# TLC5947_Breakout.net
KiCad netlist of a schematic drawn in EAGLE
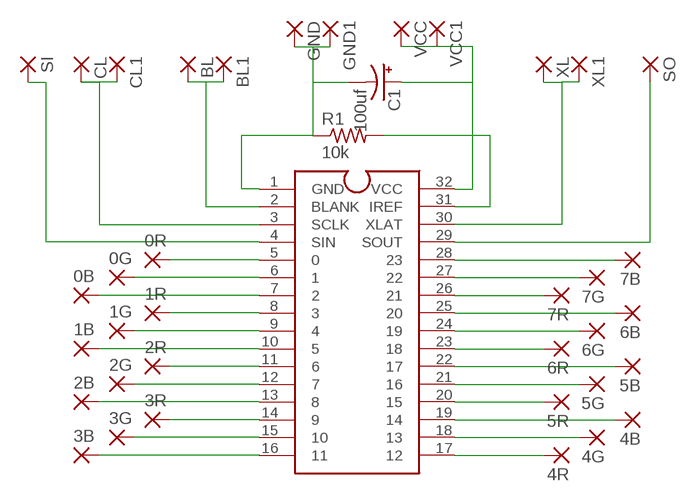
[diagram p0: schematic, sheet 1]

(export (version "E")
  (design (tool "Eeschema 10.0.6"))
  (components
    (comp (ref "0B")
      (value "SMD2")
      (footprint "eagle-import:SMD1,27-2,54")
      (libsource (lib "eagle-import") (part "SMD2"))
    )
    (comp (ref "0G")
      (value "SMD2")
      (footprint "eagle-import:SMD1,27-2,54")
      (libsource (lib "eagle-import") (part "SMD2"))
    )
    (comp (ref "0R")
      (value "SMD2")
      (footprint "eagle-import:SMD1,27-2,54")
      (libsource (lib "eagle-import") (part "SMD2"))
    )
    (comp (ref "1B")
      (value "SMD2")
      (footprint "eagle-import:SMD1,27-2,54")
      (libsource (lib "eagle-import") (part "SMD2"))
    )
    (comp (ref "1G")
      (value "SMD2")
      (footprint "eagle-import:SMD1,27-2,54")
      (libsource (lib "eagle-import") (part "SMD2"))
    )
    (comp (ref "1R")
      (value "SMD2")
      (footprint "eagle-import:SMD1,27-2,54")
      (libsource (lib "eagle-import") (part "SMD2"))
    )
    (comp (ref "2B")
      (value "SMD2")
      (footprint "eagle-import:SMD1,27-2,54")
      (libsource (lib "eagle-import") (part "SMD2"))
    )
    (comp (ref "2G")
      (value "SMD2")
      (footprint "eagle-import:SMD1,27-2,54")
      (libsource (lib "eagle-import") (part "SMD2"))
    )
    (comp (ref "2R")
      (value "SMD2")
      (footprint "eagle-import:SMD1,27-2,54")
      (libsource (lib "eagle-import") (part "SMD2"))
    )
    (comp (ref "3B")
      (value "SMD2")
      (footprint "eagle-import:SMD1,27-2,54")
      (libsource (lib "eagle-import") (part "SMD2"))
    )
    (comp (ref "3G")
      (value "SMD2")
      (footprint "eagle-import:SMD1,27-2,54")
      (libsource (lib "eagle-import") (part "SMD2"))
    )
    (comp (ref "3R")
      (value "SMD2")
      (footprint "eagle-import:SMD1,27-2,54")
      (libsource (lib "eagle-import") (part "SMD2"))
    )
    (comp (ref "4B")
      (value "SMD2")
      (footprint "eagle-import:SMD1,27-2,54")
      (libsource (lib "eagle-import") (part "SMD2"))
    )
    (comp (ref "4G")
      (value "SMD2")
      (footprint "eagle-import:SMD1,27-2,54")
      (libsource (lib "eagle-import") (part "SMD2"))
    )
    (comp (ref "4R")
      (value "SMD2")
      (footprint "eagle-import:SMD1,27-2,54")
      (libsource (lib "eagle-import") (part "SMD2"))
    )
    (comp (ref "5B")
      (value "SMD2")
      (footprint "eagle-import:SMD1,27-2,54")
      (libsource (lib "eagle-import") (part "SMD2"))
    )
    (comp (ref "5G")
      (value "SMD2")
      (footprint "eagle-import:SMD1,27-2,54")
      (libsource (lib "eagle-import") (part "SMD2"))
    )
    (comp (ref "5R")
      (value "SMD2")
      (footprint "eagle-import:SMD1,27-2,54")
      (libsource (lib "eagle-import") (part "SMD2"))
    )
    (comp (ref "6B")
      (value "SMD2")
      (footprint "eagle-import:SMD1,27-2,54")
      (libsource (lib "eagle-import") (part "SMD2"))
    )
    (comp (ref "6G")
      (value "SMD2")
      (footprint "eagle-import:SMD1,27-2,54")
      (libsource (lib "eagle-import") (part "SMD2"))
    )
    (comp (ref "6R")
      (value "SMD2")
      (footprint "eagle-import:SMD1,27-2,54")
      (libsource (lib "eagle-import") (part "SMD2"))
    )
    (comp (ref "7B")
      (value "SMD2")
      (footprint "eagle-import:SMD1,27-2,54")
      (libsource (lib "eagle-import") (part "SMD2"))
    )
    (comp (ref "7G")
      (value "SMD2")
      (footprint "eagle-import:SMD1,27-2,54")
      (libsource (lib "eagle-import") (part "SMD2"))
    )
    (comp (ref "7R")
      (value "SMD2")
      (footprint "eagle-import:SMD1,27-2,54")
      (libsource (lib "eagle-import") (part "SMD2"))
    )
    (comp (ref "BL")
      (value "SMD2")
      (footprint "eagle-import:SMD1,27-2,54")
      (libsource (lib "eagle-import") (part "SMD2"))
    )
    (comp (ref "BL1")
      (value "SMD2")
      (footprint "eagle-import:SMD1,27-2,54")
      (libsource (lib "eagle-import") (part "SMD2"))
    )
    (comp (ref "C1")
      (value "100uf")
      (footprint "eagle-import:E2,5-6")
      (libsource (lib "eagle-import") (part "CPOL-USE2.5-6"))
    )
    (comp (ref "CL")
      (value "SMD2")
      (footprint "eagle-import:SMD1,27-2,54")
      (libsource (lib "eagle-import") (part "SMD2"))
    )
    (comp (ref "CL1")
      (value "SMD2")
      (footprint "eagle-import:SMD1,27-2,54")
      (libsource (lib "eagle-import") (part "SMD2"))
    )
    (comp (ref "GND")
      (value "SMD2")
      (footprint "eagle-import:SMD1,27-2,54")
      (libsource (lib "eagle-import") (part "SMD2"))
    )
    (comp (ref "GND1")
      (value "SMD2")
      (footprint "eagle-import:SMD1,27-2,54")
      (libsource (lib "eagle-import") (part "SMD2"))
    )
    (comp (ref "R1")
      (value "10k")
      (footprint "eagle-import:0207_10")
      (libsource (lib "eagle-import") (part "R-US_0207/10"))
    )
    (comp (ref "SI")
      (value "SMD2")
      (footprint "eagle-import:SMD1,27-2,54")
      (libsource (lib "eagle-import") (part "SMD2"))
    )
    (comp (ref "SO")
      (value "SMD2")
      (footprint "eagle-import:SMD1,27-2,54")
      (libsource (lib "eagle-import") (part "SMD2"))
    )
    (comp (ref "U$1")
      (value "TLC5947DAC")
      (footprint "eagle-import:DAP38")
      (libsource (lib "eagle-import") (part "TLC5947DAC"))
    )
    (comp (ref "VCC")
      (value "SMD2")
      (footprint "eagle-import:SMD1,27-2,54")
      (libsource (lib "eagle-import") (part "SMD2"))
    )
    (comp (ref "VCC1")
      (value "SMD2")
      (footprint "eagle-import:SMD1,27-2,54")
      (libsource (lib "eagle-import") (part "SMD2"))
    )
    (comp (ref "XL")
      (value "SMD2")
      (footprint "eagle-import:SMD1,27-2,54")
      (libsource (lib "eagle-import") (part "SMD2"))
    )
    (comp (ref "XL1")
      (value "SMD2")
      (footprint "eagle-import:SMD1,27-2,54")
      (libsource (lib "eagle-import") (part "SMD2"))
    )
  )
  (nets
    (net (code "1") (name "Net-(0B-P)") (class "Default")
      (node (ref "0B") (pin "1") (pinfunction "P_1") (pintype "passive"))
      (node (ref "U$1") (pin "7") (pinfunction "2_7") (pintype "bidirectional"))
    )
    (net (code "2") (name "Net-(0G-P)") (class "Default")
      (node (ref "0G") (pin "1") (pinfunction "P_1") (pintype "passive"))
      (node (ref "U$1") (pin "6") (pinfunction "1_6") (pintype "bidirectional"))
    )
    (net (code "3") (name "Net-(0R-P)") (class "Default")
      (node (ref "0R") (pin "1") (pinfunction "P_1") (pintype "passive"))
      (node (ref "U$1") (pin "5") (pinfunction "0_5") (pintype "bidirectional"))
    )
    (net (code "4") (name "Net-(1B-P)") (class "Default")
      (node (ref "1B") (pin "1") (pinfunction "P_1") (pintype "passive"))
      (node (ref "U$1") (pin "10") (pinfunction "5_10") (pintype "bidirectional"))
    )
    (net (code "5") (name "Net-(1G-P)") (class "Default")
      (node (ref "1G") (pin "1") (pinfunction "P_1") (pintype "passive"))
      (node (ref "U$1") (pin "9") (pinfunction "4_9") (pintype "bidirectional"))
    )
    (net (code "6") (name "Net-(1R-P)") (class "Default")
      (node (ref "1R") (pin "1") (pinfunction "P_1") (pintype "passive"))
      (node (ref "U$1") (pin "8") (pinfunction "3_8") (pintype "bidirectional"))
    )
    (net (code "7") (name "Net-(2B-P)") (class "Default")
      (node (ref "2B") (pin "1") (pinfunction "P_1") (pintype "passive"))
      (node (ref "U$1") (pin "13") (pinfunction "8_13") (pintype "bidirectional"))
    )
    (net (code "8") (name "Net-(2G-P)") (class "Default")
      (node (ref "2G") (pin "1") (pinfunction "P_1") (pintype "passive"))
      (node (ref "U$1") (pin "12") (pinfunction "7_12") (pintype "bidirectional"))
    )
    (net (code "9") (name "Net-(2R-P)") (class "Default")
      (node (ref "2R") (pin "1") (pinfunction "P_1") (pintype "passive"))
      (node (ref "U$1") (pin "11") (pinfunction "6_11") (pintype "bidirectional"))
    )
    (net (code "10") (name "Net-(3B-P)") (class "Default")
      (node (ref "3B") (pin "1") (pinfunction "P_1") (pintype "passive"))
      (node (ref "U$1") (pin "16") (pinfunction "11_16") (pintype "bidirectional"))
    )
    (net (code "11") (name "Net-(3G-P)") (class "Default")
      (node (ref "3G") (pin "1") (pinfunction "P_1") (pintype "passive"))
      (node (ref "U$1") (pin "15") (pinfunction "10_15") (pintype "bidirectional"))
    )
    (net (code "12") (name "Net-(3R-P)") (class "Default")
      (node (ref "3R") (pin "1") (pinfunction "P_1") (pintype "passive"))
      (node (ref "U$1") (pin "14") (pinfunction "9_14") (pintype "bidirectional"))
    )
    (net (code "13") (name "Net-(4B-P)") (class "Default")
      (node (ref "4B") (pin "1") (pinfunction "P_1") (pintype "passive"))
      (node (ref "U$1") (pin "19") (pinfunction "14_19") (pintype "bidirectional"))
    )
    (net (code "14") (name "Net-(4G-P)") (class "Default")
      (node (ref "4G") (pin "1") (pinfunction "P_1") (pintype "passive"))
      (node (ref "U$1") (pin "18") (pinfunction "13_18") (pintype "bidirectional"))
    )
    (net (code "15") (name "Net-(4R-P)") (class "Default")
      (node (ref "4R") (pin "1") (pinfunction "P_1") (pintype "passive"))
      (node (ref "U$1") (pin "17") (pinfunction "12_17") (pintype "bidirectional"))
    )
    (net (code "16") (name "Net-(5B-P)") (class "Default")
      (node (ref "5B") (pin "1") (pinfunction "P_1") (pintype "passive"))
      (node (ref "U$1") (pin "22") (pinfunction "17_22") (pintype "bidirectional"))
    )
    (net (code "17") (name "Net-(5G-P)") (class "Default")
      (node (ref "5G") (pin "1") (pinfunction "P_1") (pintype "passive"))
      (node (ref "U$1") (pin "21") (pinfunction "16_21") (pintype "bidirectional"))
    )
    (net (code "18") (name "Net-(5R-P)") (class "Default")
      (node (ref "5R") (pin "1") (pinfunction "P_1") (pintype "passive"))
      (node (ref "U$1") (pin "20") (pinfunction "15_20") (pintype "bidirectional"))
    )
    (net (code "19") (name "Net-(6B-P)") (class "Default")
      (node (ref "6B") (pin "1") (pinfunction "P_1") (pintype "passive"))
      (node (ref "U$1") (pin "25") (pinfunction "20_25") (pintype "bidirectional"))
    )
    (net (code "20") (name "Net-(6G-P)") (class "Default")
      (node (ref "6G") (pin "1") (pinfunction "P_1") (pintype "passive"))
      (node (ref "U$1") (pin "24") (pinfunction "19_24") (pintype "bidirectional"))
    )
    (net (code "21") (name "Net-(6R-P)") (class "Default")
      (node (ref "6R") (pin "1") (pinfunction "P_1") (pintype "passive"))
      (node (ref "U$1") (pin "23") (pinfunction "18_23") (pintype "bidirectional"))
    )
    (net (code "22") (name "Net-(7B-P)") (class "Default")
      (node (ref "7B") (pin "1") (pinfunction "P_1") (pintype "passive"))
      (node (ref "U$1") (pin "28") (pinfunction "23_28") (pintype "bidirectional"))
    )
    (net (code "23") (name "Net-(7G-P)") (class "Default")
      (node (ref "7G") (pin "1") (pinfunction "P_1") (pintype "passive"))
      (node (ref "U$1") (pin "27") (pinfunction "22_27") (pintype "bidirectional"))
    )
    (net (code "24") (name "Net-(7R-P)") (class "Default")
      (node (ref "7R") (pin "1") (pinfunction "P_1") (pintype "passive"))
      (node (ref "U$1") (pin "26") (pinfunction "21_26") (pintype "bidirectional"))
    )
    (net (code "25") (name "Net-(BL-P)") (class "Default")
      (node (ref "BL") (pin "1") (pinfunction "P_1") (pintype "passive"))
      (node (ref "BL1") (pin "1") (pinfunction "P_1") (pintype "passive"))
      (node (ref "U$1") (pin "2") (pinfunction "BLANK_2") (pintype "bidirectional"))
    )
    (net (code "26") (name "Net-(CL-P)") (class "Default")
      (node (ref "CL") (pin "1") (pinfunction "P_1") (pintype "passive"))
      (node (ref "CL1") (pin "1") (pinfunction "P_1") (pintype "passive"))
      (node (ref "U$1") (pin "3") (pinfunction "SCLK_3") (pintype "bidirectional"))
    )
    (net (code "27") (name "Net-(GND-P)") (class "Default")
      (node (ref "C1") (pin "-") (pinfunction "-_-") (pintype "passive"))
      (node (ref "GND") (pin "1") (pinfunction "P_1") (pintype "passive"))
      (node (ref "GND1") (pin "1") (pinfunction "P_1") (pintype "passive"))
      (node (ref "R1") (pin "1") (pinfunction "1_1") (pintype "passive"))
      (node (ref "U$1") (pin "1") (pinfunction "GND_1") (pintype "bidirectional"))
    )
    (net (code "28") (name "Net-(SI-P)") (class "Default")
      (node (ref "SI") (pin "1") (pinfunction "P_1") (pintype "passive"))
      (node (ref "U$1") (pin "4") (pinfunction "SIN_4") (pintype "bidirectional"))
    )
    (net (code "29") (name "Net-(SO-P)") (class "Default")
      (node (ref "SO") (pin "1") (pinfunction "P_1") (pintype "passive"))
      (node (ref "U$1") (pin "29") (pinfunction "SOUT_29") (pintype "bidirectional"))
    )
    (net (code "30") (name "Net-(U$1-IREF)") (class "Default")
      (node (ref "R1") (pin "2") (pinfunction "2_2") (pintype "passive"))
      (node (ref "U$1") (pin "31") (pinfunction "IREF_31") (pintype "bidirectional"))
    )
    (net (code "31") (name "Net-(U$1-VCC)") (class "Default")
      (node (ref "C1") (pin "+") (pinfunction "+_+") (pintype "passive"))
      (node (ref "U$1") (pin "32") (pinfunction "VCC_32") (pintype "bidirectional"))
      (node (ref "VCC") (pin "1") (pinfunction "P_1") (pintype "passive"))
      (node (ref "VCC1") (pin "1") (pinfunction "P_1") (pintype "passive"))
    )
    (net (code "32") (name "Net-(U$1-XLAT)") (class "Default")
      (node (ref "U$1") (pin "30") (pinfunction "XLAT_30") (pintype "bidirectional"))
      (node (ref "XL") (pin "1") (pinfunction "P_1") (pintype "passive"))
      (node (ref "XL1") (pin "1") (pinfunction "P_1") (pintype "passive"))
    )
  )
)
